# Main_Board.net
KiCad netlist of a schematic drawn in Altium Designer
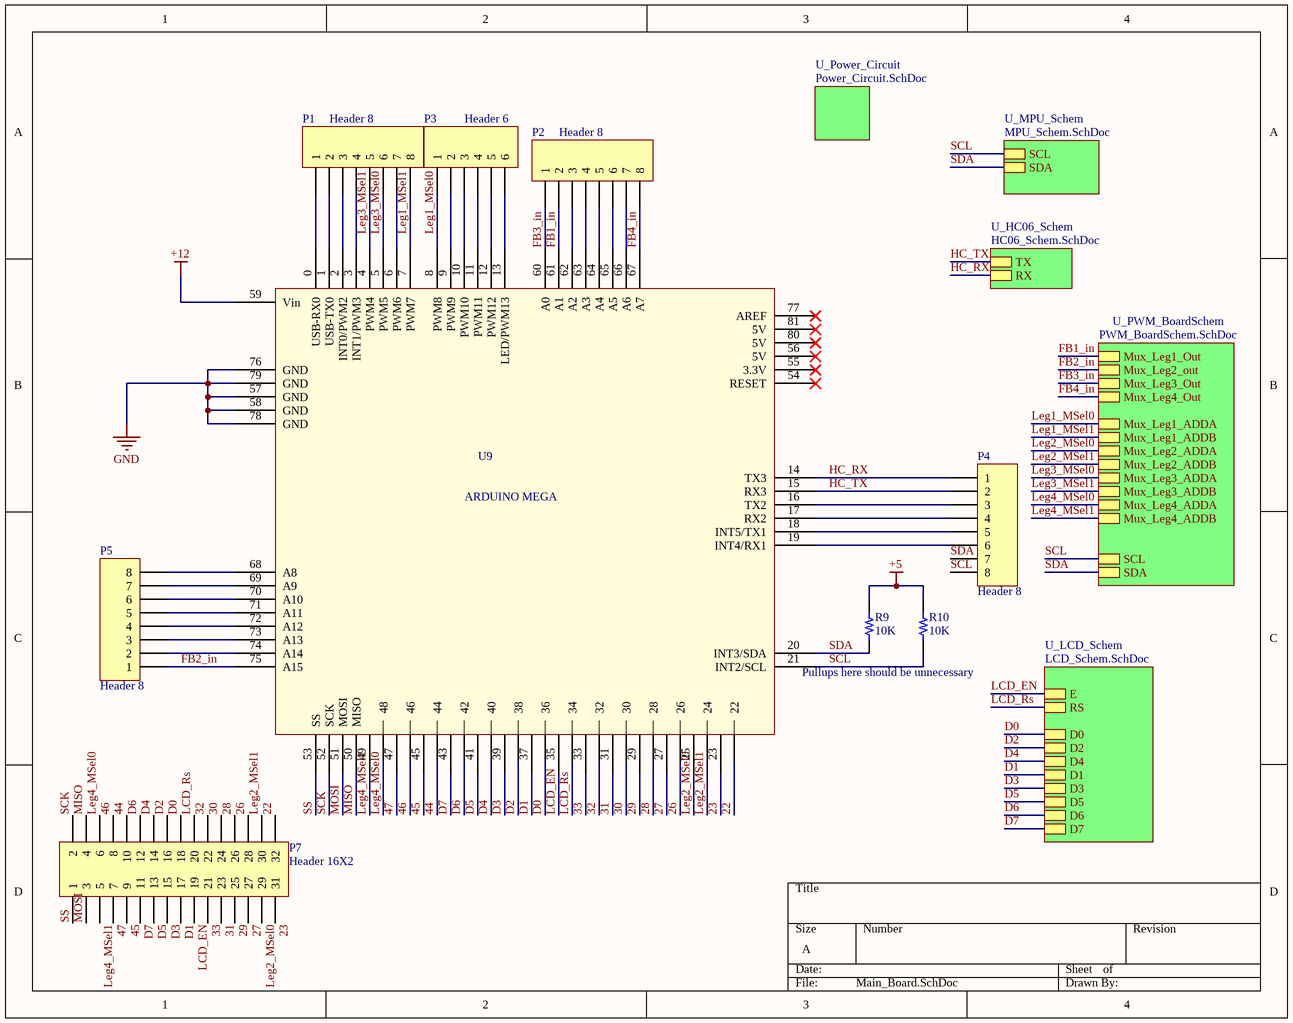
[diagram p0: Main_Board.SchDoc]

(export (version "E")
  (design (tool "Eeschema 10.0.6"))
  (components
    (comp (ref "P1")
      (value "Header 8")
      (footprint "HDR1X8")
      (description "Header, 8-Pin")
      (fields (field (name "PUBLISHER") "Altium Limited"))
      (libsource (lib "") (part "Header 8_1"))
    )
    (comp (ref "P2")
      (value "Header 8")
      (footprint "HDR1X8")
      (description "Header, 8-Pin")
      (fields (field (name "PUBLISHER") "Altium Limited"))
      (libsource (lib "") (part "Header 8_1"))
    )
    (comp (ref "P3")
      (value "Header 6")
      (footprint "HDR1X6")
      (description "Header, 6-Pin")
      (fields (field (name "PUBLISHER") "Altium Limited"))
      (libsource (lib "Miscellaneous Connectors") (part "Header 6"))
    )
    (comp (ref "P4")
      (value "Header 8")
      (footprint "HDR1X8")
      (description "Header, 8-Pin")
      (fields (field (name "PUBLISHER") "Altium Limited"))
      (libsource (lib "") (part "Header 8_2"))
    )
    (comp (ref "P5")
      (value "Header 8")
      (footprint "HDR1X8")
      (description "Header, 8-Pin")
      (fields (field (name "PUBLISHER") "Altium Limited"))
      (libsource (lib "Miscellaneous Connectors") (part "Header 8"))
    )
    (comp (ref "P7")
      (value "Header 16X2")
      (footprint "HDR2X16")
      (description "Header, 16-Pin, Dual row")
      (fields (field (name "PUBLISHER") "Altium Limited"))
      (libsource (lib "Miscellaneous Connectors") (part "Header 16X2"))
    )
    (comp (ref "R9")
      (value "10K")
      (footprint "RES 1206_3216")
      (description "RES SMD 10K OHM 1% 1/2W 1206")
      (fields (field (name "PART NUMBER") "ESR18EZPF1002") (field (name "MANUFACTURER") "Rohm Semiconductor"))
      (libsource (lib "Celestial Altium Library - altium_library") (part "Resistor"))
    )
    (comp (ref "R10")
      (value "10K")
      (footprint "RES 1206_3216")
      (description "RES SMD 10K OHM 1% 1/2W 1206")
      (fields (field (name "PART NUMBER") "ESR18EZPF1002") (field (name "MANUFACTURER") "Rohm Semiconductor"))
      (libsource (lib "Celestial Altium Library - altium_library") (part "Resistor"))
    )
    (comp (ref "U9")
      (value "ARDUINO MEGA")
      (footprint "ARDUINO MEGA")
      (libsource (lib "Arduino") (part "ARDUINO MEGA"))
    )
  )
  (nets
    (net (code "1") (name "+5") (class "Default")
      (node (ref "R10") (pin "2") (pinfunction "2_2") (pintype "passive"))
      (node (ref "R9") (pin "2") (pinfunction "2_2") (pintype "passive"))
    )
    (net (code "2") (name "+12") (class "Default")
      (node (ref "U9") (pin "59") (pinfunction "Vin_59") (pintype "passive"))
    )
    (net (code "3") (name "/22") (class "Default")
      (node (ref "P7") (pin "32") (pinfunction "32_32") (pintype "passive"))
      (node (ref "U9") (pin "22") (pinfunction "22_22") (pintype "passive"))
    )
    (net (code "4") (name "/23") (class "Default")
      (node (ref "P7") (pin "31") (pinfunction "31_31") (pintype "passive"))
      (node (ref "U9") (pin "23") (pinfunction "23_23") (pintype "passive"))
    )
    (net (code "5") (name "/26") (class "Default")
      (node (ref "P7") (pin "28") (pinfunction "28_28") (pintype "passive"))
      (node (ref "U9") (pin "26") (pinfunction "26_26") (pintype "passive"))
    )
    (net (code "6") (name "/27") (class "Default")
      (node (ref "P7") (pin "27") (pinfunction "27_27") (pintype "passive"))
      (node (ref "U9") (pin "27") (pinfunction "27_27") (pintype "passive"))
    )
    (net (code "7") (name "/28") (class "Default")
      (node (ref "P7") (pin "26") (pinfunction "26_26") (pintype "passive"))
      (node (ref "U9") (pin "28") (pinfunction "28_28") (pintype "passive"))
    )
    (net (code "8") (name "/29") (class "Default")
      (node (ref "P7") (pin "25") (pinfunction "25_25") (pintype "passive"))
      (node (ref "U9") (pin "29") (pinfunction "29_29") (pintype "passive"))
    )
    (net (code "9") (name "/30") (class "Default")
      (node (ref "P7") (pin "24") (pinfunction "24_24") (pintype "passive"))
      (node (ref "U9") (pin "30") (pinfunction "30_30") (pintype "passive"))
    )
    (net (code "10") (name "/31") (class "Default")
      (node (ref "P7") (pin "23") (pinfunction "23_23") (pintype "passive"))
      (node (ref "U9") (pin "31") (pinfunction "31_31") (pintype "passive"))
    )
    (net (code "11") (name "/32") (class "Default")
      (node (ref "P7") (pin "22") (pinfunction "22_22") (pintype "passive"))
      (node (ref "U9") (pin "32") (pinfunction "32_32") (pintype "passive"))
    )
    (net (code "12") (name "/33") (class "Default")
      (node (ref "P7") (pin "21") (pinfunction "21_21") (pintype "passive"))
      (node (ref "U9") (pin "33") (pinfunction "33_33") (pintype "passive"))
    )
    (net (code "13") (name "/44") (class "Default")
      (node (ref "P7") (pin "10") (pinfunction "10_10") (pintype "passive"))
      (node (ref "U9") (pin "44") (pinfunction "44_44") (pintype "passive"))
    )
    (net (code "14") (name "/45") (class "Default")
      (node (ref "P7") (pin "9") (pinfunction "9_9") (pintype "passive"))
      (node (ref "U9") (pin "45") (pinfunction "45_45") (pintype "passive"))
    )
    (net (code "15") (name "/46") (class "Default")
      (node (ref "P7") (pin "8") (pinfunction "8_8") (pintype "passive"))
      (node (ref "U9") (pin "46") (pinfunction "46_46") (pintype "passive"))
    )
    (net (code "16") (name "/47") (class "Default")
      (node (ref "P7") (pin "7") (pinfunction "7_7") (pintype "passive"))
      (node (ref "U9") (pin "47") (pinfunction "47_47") (pintype "passive"))
    )
    (net (code "17") (name "/D0") (class "Default")
      (node (ref "P7") (pin "18") (pinfunction "18_18") (pintype "passive"))
      (node (ref "U9") (pin "36") (pinfunction "36_36") (pintype "passive"))
    )
    (net (code "18") (name "/D1") (class "Default")
      (node (ref "P7") (pin "17") (pinfunction "17_17") (pintype "passive"))
      (node (ref "U9") (pin "37") (pinfunction "37_37") (pintype "passive"))
    )
    (net (code "19") (name "/D2") (class "Default")
      (node (ref "P7") (pin "16") (pinfunction "16_16") (pintype "passive"))
      (node (ref "U9") (pin "38") (pinfunction "38_38") (pintype "passive"))
    )
    (net (code "20") (name "/D3") (class "Default")
      (node (ref "P7") (pin "15") (pinfunction "15_15") (pintype "passive"))
      (node (ref "U9") (pin "39") (pinfunction "39_39") (pintype "passive"))
    )
    (net (code "21") (name "/D4") (class "Default")
      (node (ref "P7") (pin "14") (pinfunction "14_14") (pintype "passive"))
      (node (ref "U9") (pin "40") (pinfunction "40_40") (pintype "passive"))
    )
    (net (code "22") (name "/D5") (class "Default")
      (node (ref "P7") (pin "13") (pinfunction "13_13") (pintype "passive"))
      (node (ref "U9") (pin "41") (pinfunction "41_41") (pintype "passive"))
    )
    (net (code "23") (name "/D6") (class "Default")
      (node (ref "P7") (pin "12") (pinfunction "12_12") (pintype "passive"))
      (node (ref "U9") (pin "42") (pinfunction "42_42") (pintype "passive"))
    )
    (net (code "24") (name "/D7") (class "Default")
      (node (ref "P7") (pin "11") (pinfunction "11_11") (pintype "passive"))
      (node (ref "U9") (pin "43") (pinfunction "43_43") (pintype "passive"))
    )
    (net (code "25") (name "/FB1_in") (class "Default")
      (node (ref "P2") (pin "2") (pinfunction "2_2") (pintype "passive"))
      (node (ref "U9") (pin "61") (pinfunction "A1_61") (pintype "passive"))
    )
    (net (code "26") (name "/FB2_in") (class "Default")
      (node (ref "P5") (pin "1") (pinfunction "1_1") (pintype "passive"))
      (node (ref "U9") (pin "75") (pinfunction "A15_75") (pintype "passive"))
    )
    (net (code "27") (name "/FB3_in") (class "Default")
      (node (ref "P2") (pin "1") (pinfunction "1_1") (pintype "passive"))
      (node (ref "U9") (pin "60") (pinfunction "A0_60") (pintype "passive"))
    )
    (net (code "28") (name "/FB4_in") (class "Default")
      (node (ref "P2") (pin "8") (pinfunction "8_8") (pintype "passive"))
      (node (ref "U9") (pin "67") (pinfunction "A7_67") (pintype "passive"))
    )
    (net (code "29") (name "/HC_RX") (class "Default")
      (node (ref "P4") (pin "1") (pinfunction "1_1") (pintype "passive"))
      (node (ref "U9") (pin "14") (pinfunction "TX3_14") (pintype "passive"))
    )
    (net (code "30") (name "/HC_TX") (class "Default")
      (node (ref "P4") (pin "2") (pinfunction "2_2") (pintype "passive"))
      (node (ref "U9") (pin "15") (pinfunction "RX3_15") (pintype "passive"))
    )
    (net (code "31") (name "/LCD_EN") (class "Default")
      (node (ref "P7") (pin "19") (pinfunction "19_19") (pintype "passive"))
      (node (ref "U9") (pin "35") (pinfunction "35_35") (pintype "passive"))
    )
    (net (code "32") (name "/LCD_Rs") (class "Default")
      (node (ref "P7") (pin "20") (pinfunction "20_20") (pintype "passive"))
      (node (ref "U9") (pin "34") (pinfunction "34_34") (pintype "passive"))
    )
    (net (code "33") (name "/Leg1_MSel0") (class "Default")
      (node (ref "P3") (pin "1") (pinfunction "1_1") (pintype "passive"))
      (node (ref "U9") (pin "8") (pinfunction "PWM8_8") (pintype "passive"))
    )
    (net (code "34") (name "/Leg1_MSel1") (class "Default")
      (node (ref "P1") (pin "8") (pinfunction "8_8") (pintype "passive"))
      (node (ref "U9") (pin "7") (pinfunction "PWM7_7") (pintype "passive"))
    )
    (net (code "35") (name "/Leg2_MSel0") (class "Default")
      (node (ref "P7") (pin "29") (pinfunction "29_29") (pintype "passive"))
      (node (ref "U9") (pin "25") (pinfunction "25_25") (pintype "passive"))
    )
    (net (code "36") (name "/Leg2_MSel1") (class "Default")
      (node (ref "P7") (pin "30") (pinfunction "30_30") (pintype "passive"))
      (node (ref "U9") (pin "24") (pinfunction "24_24") (pintype "passive"))
    )
    (net (code "37") (name "/Leg3_MSel0") (class "Default")
      (node (ref "P1") (pin "6") (pinfunction "6_6") (pintype "passive"))
      (node (ref "U9") (pin "5") (pinfunction "PWM5_5") (pintype "passive"))
    )
    (net (code "38") (name "/Leg3_MSel1") (class "Default")
      (node (ref "P1") (pin "5") (pinfunction "5_5") (pintype "passive"))
      (node (ref "U9") (pin "4") (pinfunction "PWM4_4") (pintype "passive"))
    )
    (net (code "39") (name "/Leg4_MSel0") (class "Default")
      (node (ref "P7") (pin "6") (pinfunction "6_6") (pintype "passive"))
      (node (ref "U9") (pin "48") (pinfunction "48_48") (pintype "passive"))
    )
    (net (code "40") (name "/Leg4_MSel1") (class "Default")
      (node (ref "P7") (pin "5") (pinfunction "5_5") (pintype "passive"))
      (node (ref "U9") (pin "49") (pinfunction "49_49") (pintype "passive"))
    )
    (net (code "41") (name "/MISO") (class "Default")
      (node (ref "P7") (pin "4") (pinfunction "4_4") (pintype "passive"))
      (node (ref "U9") (pin "50") (pinfunction "MISO_50") (pintype "passive"))
    )
    (net (code "42") (name "/MOSI") (class "Default")
      (node (ref "P7") (pin "3") (pinfunction "3_3") (pintype "passive"))
      (node (ref "U9") (pin "51") (pinfunction "MOSI_51") (pintype "passive"))
    )
    (net (code "43") (name "/SCK") (class "Default")
      (node (ref "P7") (pin "2") (pinfunction "2_2") (pintype "passive"))
      (node (ref "U9") (pin "52") (pinfunction "SCK_52") (pintype "passive"))
    )
    (net (code "44") (name "/SCL") (class "Default")
      (node (ref "P4") (pin "8") (pinfunction "8_8") (pintype "passive"))
      (node (ref "R10") (pin "1") (pinfunction "1_1") (pintype "passive"))
      (node (ref "U9") (pin "21") (pinfunction "INT2/SCL_21") (pintype "passive"))
    )
    (net (code "45") (name "/SDA") (class "Default")
      (node (ref "P4") (pin "7") (pinfunction "7_7") (pintype "passive"))
      (node (ref "R9") (pin "1") (pinfunction "1_1") (pintype "passive"))
      (node (ref "U9") (pin "20") (pinfunction "INT3/SDA_20") (pintype "passive"))
    )
    (net (code "46") (name "/SS") (class "Default")
      (node (ref "P7") (pin "1") (pinfunction "1_1") (pintype "passive"))
      (node (ref "U9") (pin "53") (pinfunction "SS_53") (pintype "passive"))
    )
    (net (code "47") (name "GND") (class "Default")
      (node (ref "U9") (pin "57") (pinfunction "GND_57") (pintype "passive"))
      (node (ref "U9") (pin "58") (pinfunction "GND_58") (pintype "passive"))
      (node (ref "U9") (pin "76") (pinfunction "GND_76") (pintype "passive"))
      (node (ref "U9") (pin "78") (pinfunction "GND_78") (pintype "passive"))
      (node (ref "U9") (pin "79") (pinfunction "GND_79") (pintype "passive"))
    )
    (net (code "48") (name "Net-(U9-A2)") (class "Default")
      (node (ref "P2") (pin "3") (pinfunction "3_3") (pintype "passive"))
      (node (ref "U9") (pin "62") (pinfunction "A2_62") (pintype "passive"))
    )
    (net (code "49") (name "Net-(U9-A3)") (class "Default")
      (node (ref "P2") (pin "4") (pinfunction "4_4") (pintype "passive"))
      (node (ref "U9") (pin "63") (pinfunction "A3_63") (pintype "passive"))
    )
    (net (code "50") (name "Net-(U9-A4)") (class "Default")
      (node (ref "P2") (pin "5") (pinfunction "5_5") (pintype "passive"))
      (node (ref "U9") (pin "64") (pinfunction "A4_64") (pintype "passive"))
    )
    (net (code "51") (name "Net-(U9-A5)") (class "Default")
      (node (ref "P2") (pin "6") (pinfunction "6_6") (pintype "passive"))
      (node (ref "U9") (pin "65") (pinfunction "A5_65") (pintype "passive"))
    )
    (net (code "52") (name "Net-(U9-A6)") (class "Default")
      (node (ref "P2") (pin "7") (pinfunction "7_7") (pintype "passive"))
      (node (ref "U9") (pin "66") (pinfunction "A6_66") (pintype "passive"))
    )
    (net (code "53") (name "Net-(U9-A8)") (class "Default")
      (node (ref "P5") (pin "8") (pinfunction "8_8") (pintype "passive"))
      (node (ref "U9") (pin "68") (pinfunction "A8_68") (pintype "passive"))
    )
    (net (code "54") (name "Net-(U9-A9)") (class "Default")
      (node (ref "P5") (pin "7") (pinfunction "7_7") (pintype "passive"))
      (node (ref "U9") (pin "69") (pinfunction "A9_69") (pintype "passive"))
    )
    (net (code "55") (name "Net-(U9-A10)") (class "Default")
      (node (ref "P5") (pin "6") (pinfunction "6_6") (pintype "passive"))
      (node (ref "U9") (pin "70") (pinfunction "A10_70") (pintype "passive"))
    )
    (net (code "56") (name "Net-(U9-A11)") (class "Default")
      (node (ref "P5") (pin "5") (pinfunction "5_5") (pintype "passive"))
      (node (ref "U9") (pin "71") (pinfunction "A11_71") (pintype "passive"))
    )
    (net (code "57") (name "Net-(U9-A12)") (class "Default")
      (node (ref "P5") (pin "4") (pinfunction "4_4") (pintype "passive"))
      (node (ref "U9") (pin "72") (pinfunction "A12_72") (pintype "passive"))
    )
    (net (code "58") (name "Net-(U9-A13)") (class "Default")
      (node (ref "P5") (pin "3") (pinfunction "3_3") (pintype "passive"))
      (node (ref "U9") (pin "73") (pinfunction "A13_73") (pintype "passive"))
    )
    (net (code "59") (name "Net-(U9-A14)") (class "Default")
      (node (ref "P5") (pin "2") (pinfunction "2_2") (pintype "passive"))
      (node (ref "U9") (pin "74") (pinfunction "A14_74") (pintype "passive"))
    )
    (net (code "60") (name "Net-(U9-INT0{slash}PWM2)") (class "Default")
      (node (ref "P1") (pin "3") (pinfunction "3_3") (pintype "passive"))
      (node (ref "U9") (pin "2") (pinfunction "INT0/PWM2_2") (pintype "passive"))
    )
    (net (code "61") (name "Net-(U9-INT1{slash}PWM3)") (class "Default")
      (node (ref "P1") (pin "4") (pinfunction "4_4") (pintype "passive"))
      (node (ref "U9") (pin "3") (pinfunction "INT1/PWM3_3") (pintype "passive"))
    )
    (net (code "62") (name "Net-(U9-INT4{slash}RX1)") (class "Default")
      (node (ref "P4") (pin "6") (pinfunction "6_6") (pintype "passive"))
      (node (ref "U9") (pin "19") (pinfunction "INT4/RX1_19") (pintype "passive"))
    )
    (net (code "63") (name "Net-(U9-INT5{slash}TX1)") (class "Default")
      (node (ref "P4") (pin "5") (pinfunction "5_5") (pintype "passive"))
      (node (ref "U9") (pin "18") (pinfunction "INT5/TX1_18") (pintype "passive"))
    )
    (net (code "64") (name "Net-(U9-LED{slash}PWM13)") (class "Default")
      (node (ref "P3") (pin "6") (pinfunction "6_6") (pintype "passive"))
      (node (ref "U9") (pin "13") (pinfunction "LED/PWM13_13") (pintype "passive"))
    )
    (net (code "65") (name "Net-(U9-PWM6)") (class "Default")
      (node (ref "P1") (pin "7") (pinfunction "7_7") (pintype "passive"))
      (node (ref "U9") (pin "6") (pinfunction "PWM6_6") (pintype "passive"))
    )
    (net (code "66") (name "Net-(U9-PWM9)") (class "Default")
      (node (ref "P3") (pin "2") (pinfunction "2_2") (pintype "passive"))
      (node (ref "U9") (pin "9") (pinfunction "PWM9_9") (pintype "passive"))
    )
    (net (code "67") (name "Net-(U9-PWM10)") (class "Default")
      (node (ref "P3") (pin "3") (pinfunction "3_3") (pintype "passive"))
      (node (ref "U9") (pin "10") (pinfunction "PWM10_10") (pintype "passive"))
    )
    (net (code "68") (name "Net-(U9-PWM11)") (class "Default")
      (node (ref "P3") (pin "4") (pinfunction "4_4") (pintype "passive"))
      (node (ref "U9") (pin "11") (pinfunction "PWM11_11") (pintype "passive"))
    )
    (net (code "69") (name "Net-(U9-PWM12)") (class "Default")
      (node (ref "P3") (pin "5") (pinfunction "5_5") (pintype "passive"))
      (node (ref "U9") (pin "12") (pinfunction "PWM12_12") (pintype "passive"))
    )
    (net (code "70") (name "Net-(U9-RX2)") (class "Default")
      (node (ref "P4") (pin "4") (pinfunction "4_4") (pintype "passive"))
      (node (ref "U9") (pin "17") (pinfunction "RX2_17") (pintype "passive"))
    )
    (net (code "71") (name "Net-(U9-TX2)") (class "Default")
      (node (ref "P4") (pin "3") (pinfunction "3_3") (pintype "passive"))
      (node (ref "U9") (pin "16") (pinfunction "TX2_16") (pintype "passive"))
    )
    (net (code "72") (name "Net-(U9-USB-RX0)") (class "Default")
      (node (ref "P1") (pin "1") (pinfunction "1_1") (pintype "passive"))
      (node (ref "U9") (pin "0") (pinfunction "USB-RX0_0") (pintype "passive"))
    )
    (net (code "73") (name "Net-(U9-USB-TX0)") (class "Default")
      (node (ref "P1") (pin "2") (pinfunction "2_2") (pintype "passive"))
      (node (ref "U9") (pin "1") (pinfunction "USB-TX0_1") (pintype "passive"))
    )
    (net (code "74") (name "unconnected-(U9-3.3V-Pad55)") (class "Default")
      (node (ref "U9") (pin "55") (pinfunction "3.3V_55") (pintype "passive+no_connect"))
    )
    (net (code "75") (name "unconnected-(U9-5V-Pad56)") (class "Default")
      (node (ref "U9") (pin "56") (pinfunction "5V_56") (pintype "passive+no_connect"))
    )
    (net (code "76") (name "unconnected-(U9-5V-Pad80)") (class "Default")
      (node (ref "U9") (pin "80") (pinfunction "5V_80") (pintype "passive+no_connect"))
    )
    (net (code "77") (name "unconnected-(U9-5V-Pad81)") (class "Default")
      (node (ref "U9") (pin "81") (pinfunction "5V_81") (pintype "passive+no_connect"))
    )
    (net (code "78") (name "unconnected-(U9-AREF-Pad77)") (class "Default")
      (node (ref "U9") (pin "77") (pinfunction "AREF_77") (pintype "passive+no_connect"))
    )
    (net (code "79") (name "unconnected-(U9-RESET-Pad54)") (class "Default")
      (node (ref "U9") (pin "54") (pinfunction "RESET_54") (pintype "passive+no_connect"))
    )
  )
)
